# CH32F_V208R-R0.net
KiCad netlist of a schematic drawn in Altium Designer
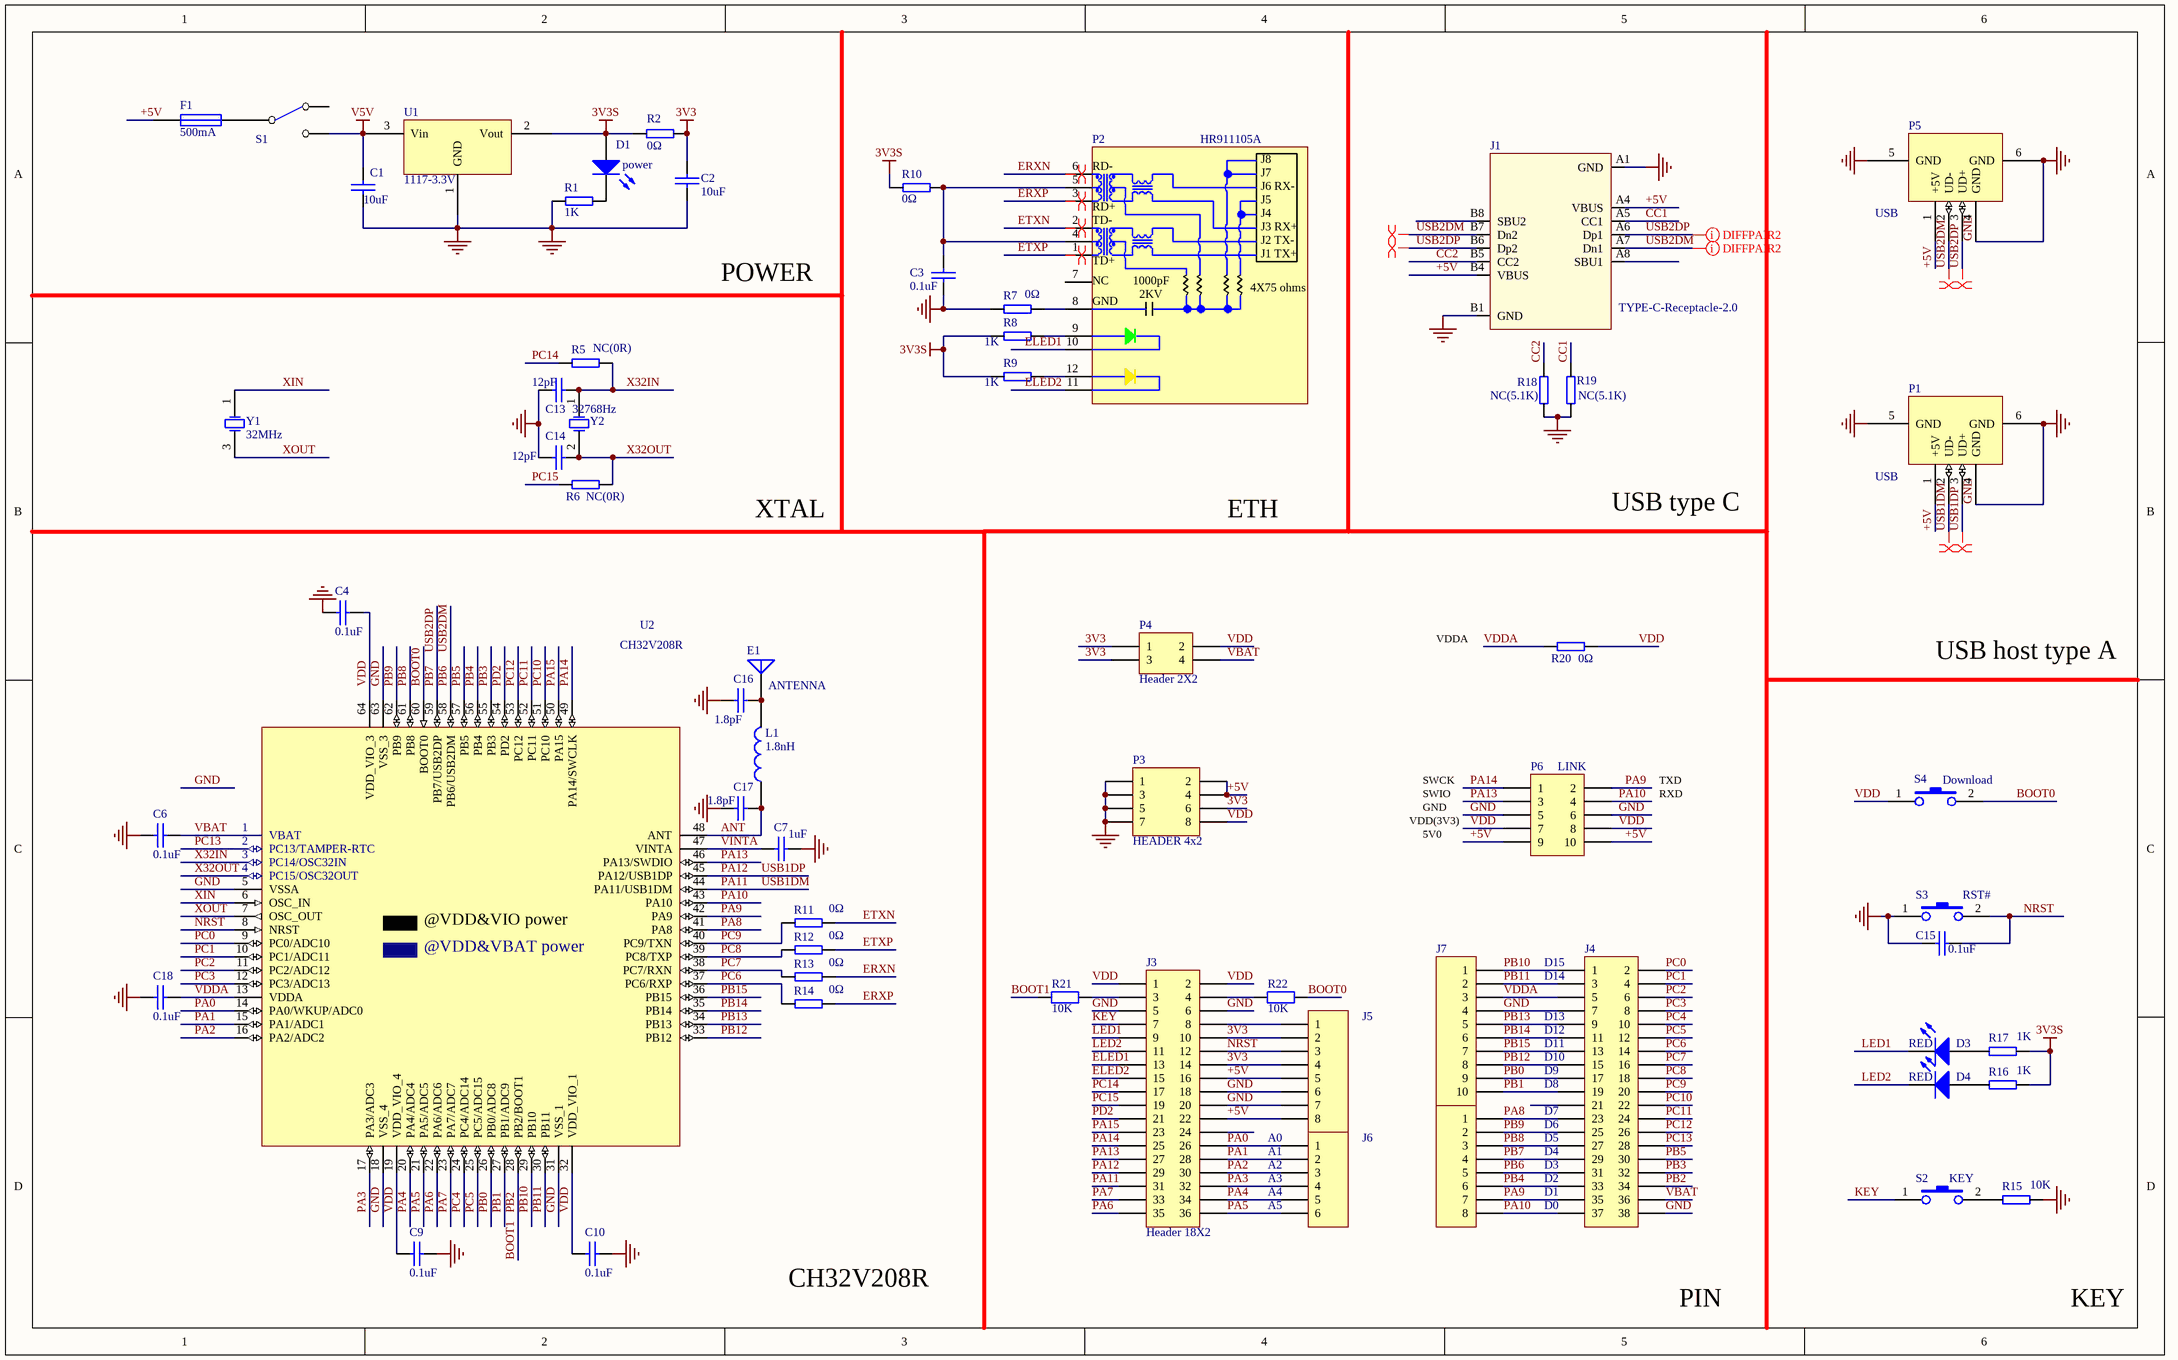
[diagram p0: CH32F&V208R-R0.SchDoc]

(export (version "E")
  (design (tool "Eeschema 10.0.6"))
  (components
    (comp (ref "C1")
      (value "10uF")
      (footprint "3216_C")
      (description "Capacitor")
      (libsource (lib "*") (part "CAP"))
    )
    (comp (ref "C2")
      (value "10uF")
      (footprint "0603_C")
      (description "Capacitor")
      (libsource (lib "*") (part "CAP"))
    )
    (comp (ref "C3")
      (value "0.1uF")
      (footprint "0603_C")
      (description "Capacitor")
      (libsource (lib "*") (part "CAP"))
    )
    (comp (ref "C4")
      (value "0.1uF")
      (footprint "0603_C")
      (description "Capacitor")
      (libsource (lib "") (part "CAP_1"))
    )
    (comp (ref "C6")
      (value "0.1uF")
      (footprint "0603_C")
      (description "Capacitor")
      (libsource (lib "") (part "CAP_1"))
    )
    (comp (ref "C7")
      (value "1uF")
      (footprint "0603_C")
      (description "Capacitor")
      (libsource (lib "") (part "CAP_1"))
    )
    (comp (ref "C9")
      (value "0.1uF")
      (footprint "0603_C")
      (description "Capacitor")
      (libsource (lib "") (part "CAP_1"))
    )
    (comp (ref "C10")
      (value "0.1uF")
      (footprint "0603_C")
      (description "Capacitor")
      (libsource (lib "") (part "CAP_1"))
    )
    (comp (ref "C13")
      (value "12pF")
      (footprint "0603_C")
      (description "Capacitor")
      (libsource (lib "*") (part "CAP"))
    )
    (comp (ref "C14")
      (value "12pF")
      (footprint "0603_C")
      (description "Capacitor")
      (libsource (lib "*") (part "CAP"))
    )
    (comp (ref "C15")
      (value "0.1uF")
      (footprint "0603_C")
      (description "Capacitor")
      (libsource (lib "") (part "CAP_1"))
    )
    (comp (ref "C16")
      (value "1.8pF")
      (footprint "0603_C")
      (description "Capacitor")
      (libsource (lib "") (part "CAP_1"))
    )
    (comp (ref "C17")
      (value "1.8pF")
      (footprint "0603_C")
      (description "Capacitor")
      (libsource (lib "") (part "CAP_1"))
    )
    (comp (ref "C18")
      (value "0.1uF")
      (footprint "0603_C")
      (description "Capacitor")
      (libsource (lib "") (part "CAP_1"))
    )
    (comp (ref "D1")
      (value "power")
      (footprint "0603+")
      (description "Typical INFRARED GaAs LED")
      (fields (field (name "PUBLISHER") "Altium Limited"))
      (libsource (lib "*") (part "LED0"))
    )
    (comp (ref "D3")
      (value "RED")
      (footprint "0603+")
      (description "Typical INFRARED GaAs LED")
      (fields (field (name "PUBLISHER") "Altium Limited"))
      (libsource (lib "*") (part "LED0"))
    )
    (comp (ref "D4")
      (value "RED")
      (footprint "0603+")
      (description "Typical INFRARED GaAs LED")
      (fields (field (name "PUBLISHER") "Altium Limited"))
      (libsource (lib "*") (part "LED0"))
    )
    (comp (ref "E1")
      (value "ANTENNA")
      (footprint "MYPCB:ANT-F-1-2.4G-1.6mmFR4")
      (description "Generic Antenna")
      (libsource (lib "*") (part "ANTENNA"))
    )
    (comp (ref "F1")
      (value "500mA")
      (footprint "0603")
      (description "Fuse")
      (libsource (lib "wch_sch_others") (part "FUSE1"))
    )
    (comp (ref "J1")
      (value "TYPE-C-Receptacle-2.0")
      (footprint "TYPE-C-Receptacle-2.0")
      (description "Type-C USB2.0 母座")
      (libsource (lib "Miscellaneous SCH Lib") (part "TYPE-C-Receptacle-2.0"))
    )
    (comp (ref "J3")
      (value "Header 18X2")
      (footprint "IDC36-2.54mm")
      (description "Header, 18-Pin, Dual row")
      (fields (field (name "PUBLISHER") "Altium Limited"))
      (libsource (lib "Miscellaneous Connectors") (part "Header 18X2"))
    )
    (comp (ref "J4")
      (value "Header 19X2")
      (footprint "IDC38-2.54mm")
      (description "Header, 19-Pin, Dual row")
      (fields (field (name "PUBLISHER") "Altium Limited"))
      (libsource (lib "Miscellaneous Connectors") (part "Header 19X2"))
    )
    (comp (ref "J5")
      (value "Header 8")
      (footprint "SIP8-2.54mm")
      (description "Header, 8-Pin")
      (fields (field (name "PUBLISHER") "Altium Limited"))
      (libsource (lib "Miscellaneous Connectors") (part "Header 8"))
    )
    (comp (ref "J6")
      (value "Header 6")
      (footprint "SIP6-2.54MM")
      (description "Header, 6-Pin")
      (fields (field (name "PUBLISHER") "Altium Limited"))
      (libsource (lib "Miscellaneous Connectors") (part "Header 6"))
    )
    (comp (ref "J7")
      (value "Header 10")
      (footprint "SIP10-2.54mm")
      (description "Header, 10-Pin")
      (fields (field (name "PUBLISHER") "Altium Limited"))
      (libsource (lib "Miscellaneous Connectors") (part "Header 10"))
    )
    (comp (ref "J8")
      (value "Header 8")
      (footprint "SIP8-2.54mm")
      (description "Header, 8-Pin")
      (fields (field (name "PUBLISHER") "Altium Limited"))
      (libsource (lib "") (part "Header 8_1"))
    )
    (comp (ref "L1") (value "1.8nH") (footprint "0603") (libsource (lib "*") (part "INDUCTOR")))
    (comp (ref "P1")
      (value "USB")
      (footprint "USBAF")
      (description "USB Port")
      (libsource (lib "*") (part "USB"))
    )
    (comp (ref "P2") (value "HR911105A") (footprint "HR911105A") (libsource (lib "*") (part "HR911105A")))
    (comp (ref "P3")
      (value "HEADER 4x2")
      (footprint "MYPCB:IDC8-2.54mm")
      (description "Header, 4-Pin, Dual row")
      (libsource (lib "wch_sch_others") (part "HEADER 4x2"))
    )
    (comp (ref "P4")
      (value "Header 2X2")
      (footprint "IDC4-2.54mm")
      (description "Header, 2-Pin, Dual row")
      (fields (field (name "PUBLISHER") "Altium Limited"))
      (libsource (lib "Miscellaneous Connectors") (part "Header 2X2"))
    )
    (comp (ref "P5")
      (value "USB")
      (footprint "USBAF")
      (description "USB Port")
      (libsource (lib "*") (part "USB"))
    )
    (comp (ref "P6")
      (value "LINK")
      (footprint "IDC10-2.54mm")
      (description "Header, 5-Pin, Dual row, Right Angle")
      (fields (field (name "PUBLISHER") "Altium Limited"))
      (libsource (lib "Miscellaneous Connectors") (part "Header 5X2H"))
    )
    (comp (ref "R1") (value "1K") (footprint "0603") (libsource (lib "wch_sch_others") (part "RES")))
    (comp (ref "R2") (value "0Ω") (footprint "0603") (libsource (lib "wch_sch_others") (part "RES")))
    (comp (ref "R5") (value "NC(0R)") (footprint "0603") (libsource (lib "wch_sch_others") (part "RES")))
    (comp (ref "R6") (value "NC(0R)") (footprint "0603") (libsource (lib "wch_sch_others") (part "RES")))
    (comp (ref "R7") (value "0Ω") (footprint "0603") (libsource (lib "wch_sch_others") (part "RES")))
    (comp (ref "R8") (value "1K") (footprint "0603") (libsource (lib "wch_sch_others") (part "RES")))
    (comp (ref "R9") (value "1K") (footprint "0603") (libsource (lib "wch_sch_others") (part "RES")))
    (comp (ref "R10") (value "0Ω") (footprint "0603") (libsource (lib "wch_sch_others") (part "RES")))
    (comp (ref "R11") (value "0Ω") (footprint "0603") (libsource (lib "wch_sch_others") (part "RES")))
    (comp (ref "R12") (value "0Ω") (footprint "0603") (libsource (lib "wch_sch_others") (part "RES")))
    (comp (ref "R13") (value "0Ω") (footprint "0603") (libsource (lib "wch_sch_others") (part "RES")))
    (comp (ref "R14") (value "0Ω") (footprint "0603") (libsource (lib "wch_sch_others") (part "RES")))
    (comp (ref "R15") (value "10K") (footprint "0603") (libsource (lib "wch_sch_others") (part "RES")))
    (comp (ref "R16") (value "1K") (footprint "0603") (libsource (lib "wch_sch_others") (part "RES")))
    (comp (ref "R17") (value "1K") (footprint "0603") (libsource (lib "wch_sch_others") (part "RES")))
    (comp (ref "R18") (value "NC(5.1K)") (footprint "0603") (libsource (lib "wch_sch_others") (part "RES")))
    (comp (ref "R19") (value "NC(5.1K)") (footprint "0603") (libsource (lib "wch_sch_others") (part "RES")))
    (comp (ref "R20") (value "0Ω") (footprint "0603") (libsource (lib "*") (part "R")))
    (comp (ref "R21")
      (value "10K")
      (footprint "0603")
      (description "Resistor")
      (libsource (lib "Miscellaneous Devices") (part "Res2"))
    )
    (comp (ref "R22")
      (value "10K")
      (footprint "0603")
      (description "Resistor")
      (libsource (lib "Miscellaneous Devices") (part "Res2"))
    )
    (comp (ref "S1") (value "SW SPDT") (footprint "SW1") (libsource (lib "*") (part "SW SPDT")))
    (comp (ref "S2")
      (value "KEY")
      (footprint "SMD_6.1x3.65x2.5mm-KEY")
      (libsource (lib "wch_sch_others") (part "KEY1"))
    )
    (comp (ref "S3")
      (value "RST#")
      (footprint "SMD_6.1x3.65x2.5mm-KEY")
      (libsource (lib "wch_sch_others") (part "KEY1"))
    )
    (comp (ref "S4")
      (value "Download")
      (footprint "SMD_6.1x3.65x2.5mm-KEY")
      (libsource (lib "wch_sch_others") (part "KEY1"))
    )
    (comp (ref "U1")
      (value "1117-3.3V")
      (footprint "SOT-223")
      (libsource (lib "wch_sch_others") (part "1117-3.3V"))
    )
    (comp (ref "U2")
      (value "CH32V208R")
      (footprint "LQFP64M_10x10")
      (description "RISC-V BLE5.3 MCU, 10M Ethernet, 2*USB, CAN")
      (libsource (lib "CHXXX") (part "CH32V208R"))
    )
    (comp (ref "Y1")
      (value "32MHz")
      (footprint "XT3225")
      (description "Crystal Oscillator")
      (fields (field (name "PUBLISHER") "Altium Limited"))
      (libsource (lib "") (part "XTAL_1"))
    )
    (comp (ref "Y2")
      (value "32768Hz")
      (footprint "FC-135")
      (description "Crystal Oscillator")
      (fields (field (name "PUBLISHER") "Altium Limited"))
      (libsource (lib "*") (part "XTAL"))
    )
  )
  (nets
    (net (code "1") (name "/+5V") (class "Default")
      (node (ref "F1") (pin "1") (pinfunction "1_1") (pintype "passive"))
      (node (ref "J1") (pin "A4") (pinfunction "VBUS_A4") (pintype "passive"))
      (node (ref "J1") (pin "B4") (pinfunction "VBUS_B4") (pintype "passive"))
      (node (ref "J3") (pin "16") (pinfunction "16_16") (pintype "passive"))
      (node (ref "J3") (pin "22") (pinfunction "22_22") (pintype "passive"))
      (node (ref "J5") (pin "5") (pinfunction "5_5") (pintype "passive"))
      (node (ref "J5") (pin "8") (pinfunction "8_8") (pintype "passive"))
      (node (ref "P1") (pin "1") (pinfunction "+5V_1") (pintype "power_in"))
      (node (ref "P3") (pin "2") (pinfunction "2_2") (pintype "passive"))
      (node (ref "P3") (pin "4") (pinfunction "4_4") (pintype "passive"))
      (node (ref "P5") (pin "1") (pinfunction "+5V_1") (pintype "power_in"))
      (node (ref "P6") (pin "10") (pinfunction "10_10") (pintype "passive"))
      (node (ref "P6") (pin "9") (pinfunction "9_9") (pintype "passive"))
    )
    (net (code "2") (name "/ANT") (class "Default")
      (node (ref "C17") (pin "2") (pinfunction "2_2") (pintype "passive"))
      (node (ref "L1") (pin "1") (pinfunction "1_1") (pintype "passive"))
      (node (ref "U2") (pin "48") (pinfunction "ANT_48") (pintype "power_in"))
    )
    (net (code "3") (name "/BOOT0") (class "Default")
      (node (ref "R22") (pin "2") (pinfunction "2_2") (pintype "passive"))
      (node (ref "S4") (pin "2") (pinfunction "2_2") (pintype "passive"))
      (node (ref "U2") (pin "60") (pinfunction "BOOT0_60") (pintype "input"))
    )
    (net (code "4") (name "/BOOT1") (class "Default")
      (node (ref "J4") (pin "34") (pinfunction "34_34") (pintype "passive"))
      (node (ref "R21") (pin "1") (pinfunction "1_1") (pintype "passive"))
      (node (ref "U2") (pin "28") (pinfunction "PB2/BOOT1_28") (pintype "bidirectional"))
    )
    (net (code "5") (name "/CC1") (class "Default")
      (node (ref "J1") (pin "A5") (pinfunction "CC1_A5") (pintype "passive"))
      (node (ref "R19") (pin "1") (pintype "passive"))
    )
    (net (code "6") (name "/CC2") (class "Default")
      (node (ref "J1") (pin "B5") (pinfunction "CC2_B5") (pintype "passive"))
      (node (ref "R18") (pin "1") (pintype "passive"))
    )
    (net (code "7") (name "/ELED1") (class "Default")
      (node (ref "J3") (pin "13") (pinfunction "13_13") (pintype "passive"))
      (node (ref "P2") (pin "10") (pintype "passive"))
    )
    (net (code "8") (name "/ELED2") (class "Default")
      (node (ref "J3") (pin "15") (pinfunction "15_15") (pintype "passive"))
      (node (ref "P2") (pin "11") (pintype "passive"))
    )
    (net (code "9") (name "/ERXN") (class "Default")
      (node (ref "P2") (pin "6") (pintype "passive"))
      (node (ref "R13") (pin "2") (pintype "passive"))
    )
    (net (code "10") (name "/ERXP") (class "Default")
      (node (ref "P2") (pin "3") (pintype "passive"))
      (node (ref "R14") (pin "2") (pintype "passive"))
    )
    (net (code "11") (name "/ETXN") (class "Default")
      (node (ref "P2") (pin "2") (pintype "passive"))
      (node (ref "R11") (pin "2") (pintype "passive"))
    )
    (net (code "12") (name "/ETXP") (class "Default")
      (node (ref "P2") (pin "1") (pintype "passive"))
      (node (ref "R12") (pin "2") (pintype "passive"))
    )
    (net (code "13") (name "/KEY") (class "Default")
      (node (ref "J3") (pin "7") (pinfunction "7_7") (pintype "passive"))
      (node (ref "S2") (pin "1") (pinfunction "1_1") (pintype "passive"))
    )
    (net (code "14") (name "/LED1") (class "Default")
      (node (ref "D3") (pin "2") (pinfunction "K_2") (pintype "passive"))
      (node (ref "J3") (pin "9") (pinfunction "9_9") (pintype "passive"))
    )
    (net (code "15") (name "/LED2") (class "Default")
      (node (ref "D4") (pin "2") (pinfunction "K_2") (pintype "passive"))
      (node (ref "J3") (pin "11") (pinfunction "11_11") (pintype "passive"))
    )
    (net (code "16") (name "/NRST") (class "Default")
      (node (ref "C15") (pin "2") (pinfunction "2_2") (pintype "passive"))
      (node (ref "J3") (pin "12") (pinfunction "12_12") (pintype "passive"))
      (node (ref "J5") (pin "3") (pinfunction "3_3") (pintype "passive"))
      (node (ref "S3") (pin "2") (pinfunction "2_2") (pintype "passive"))
      (node (ref "U2") (pin "8") (pinfunction "NRST_8") (pintype "input"))
    )
    (net (code "17") (name "/PA0") (class "Default")
      (node (ref "J3") (pin "26") (pinfunction "26_26") (pintype "passive"))
      (node (ref "J6") (pin "1") (pinfunction "1_1") (pintype "passive"))
      (node (ref "U2") (pin "14") (pinfunction "PA0/WKUP/ADC0_14") (pintype "bidirectional"))
    )
    (net (code "18") (name "/PA1") (class "Default")
      (node (ref "J3") (pin "28") (pinfunction "28_28") (pintype "passive"))
      (node (ref "J6") (pin "2") (pinfunction "2_2") (pintype "passive"))
      (node (ref "U2") (pin "15") (pinfunction "PA1/ADC1_15") (pintype "bidirectional"))
    )
    (net (code "19") (name "/PA2") (class "Default")
      (node (ref "J3") (pin "30") (pinfunction "30_30") (pintype "passive"))
      (node (ref "J6") (pin "3") (pinfunction "3_3") (pintype "passive"))
      (node (ref "U2") (pin "16") (pinfunction "PA2/ADC2_16") (pintype "bidirectional"))
    )
    (net (code "20") (name "/PA3") (class "Default")
      (node (ref "J3") (pin "32") (pinfunction "32_32") (pintype "passive"))
      (node (ref "J6") (pin "4") (pinfunction "4_4") (pintype "passive"))
      (node (ref "U2") (pin "17") (pinfunction "PA3/ADC3_17") (pintype "bidirectional"))
    )
    (net (code "21") (name "/PA4") (class "Default")
      (node (ref "J3") (pin "34") (pinfunction "34_34") (pintype "passive"))
      (node (ref "J6") (pin "5") (pinfunction "5_5") (pintype "passive"))
      (node (ref "U2") (pin "20") (pinfunction "PA4/ADC4_20") (pintype "bidirectional"))
    )
    (net (code "22") (name "/PA5") (class "Default")
      (node (ref "J3") (pin "36") (pinfunction "36_36") (pintype "passive"))
      (node (ref "J6") (pin "6") (pinfunction "6_6") (pintype "passive"))
      (node (ref "U2") (pin "21") (pinfunction "PA5/ADC5_21") (pintype "bidirectional"))
    )
    (net (code "23") (name "/PA6") (class "Default")
      (node (ref "J3") (pin "35") (pinfunction "35_35") (pintype "passive"))
      (node (ref "U2") (pin "22") (pinfunction "PA6/ADC6_22") (pintype "bidirectional"))
    )
    (net (code "24") (name "/PA7") (class "Default")
      (node (ref "J3") (pin "33") (pinfunction "33_33") (pintype "passive"))
      (node (ref "U2") (pin "23") (pinfunction "PA7/ADC7_23") (pintype "bidirectional"))
    )
    (net (code "25") (name "/PA8") (class "Default")
      (node (ref "J4") (pin "23") (pinfunction "23_23") (pintype "passive"))
      (node (ref "J8") (pin "1") (pinfunction "1_1") (pintype "passive"))
      (node (ref "U2") (pin "41") (pinfunction "PA8_41") (pintype "bidirectional"))
    )
    (net (code "26") (name "/PA9") (class "Default")
      (node (ref "J4") (pin "35") (pinfunction "35_35") (pintype "passive"))
      (node (ref "J8") (pin "7") (pinfunction "7_7") (pintype "passive"))
      (node (ref "P6") (pin "2") (pinfunction "2_2") (pintype "passive"))
      (node (ref "U2") (pin "42") (pinfunction "PA9_42") (pintype "bidirectional"))
    )
    (net (code "27") (name "/PA10") (class "Default")
      (node (ref "J4") (pin "37") (pinfunction "37_37") (pintype "passive"))
      (node (ref "J8") (pin "8") (pinfunction "8_8") (pintype "passive"))
      (node (ref "P6") (pin "4") (pinfunction "4_4") (pintype "passive"))
      (node (ref "U2") (pin "43") (pinfunction "PA10_43") (pintype "bidirectional"))
    )
    (net (code "28") (name "/PA11") (class "Default")
      (node (ref "J3") (pin "31") (pinfunction "31_31") (pintype "passive"))
      (node (ref "P1") (pin "2") (pinfunction "UD-_2") (pintype "bidirectional"))
      (node (ref "U2") (pin "44") (pinfunction "PA11/USB1DM_44") (pintype "bidirectional"))
    )
    (net (code "29") (name "/PA12") (class "Default")
      (node (ref "J3") (pin "29") (pinfunction "29_29") (pintype "passive"))
      (node (ref "P1") (pin "3") (pinfunction "UD+_3") (pintype "bidirectional"))
      (node (ref "U2") (pin "45") (pinfunction "PA12/USB1DP_45") (pintype "bidirectional"))
    )
    (net (code "30") (name "/PA13") (class "Default")
      (node (ref "J3") (pin "27") (pinfunction "27_27") (pintype "passive"))
      (node (ref "P6") (pin "3") (pinfunction "3_3") (pintype "passive"))
      (node (ref "U2") (pin "46") (pinfunction "PA13/SWDIO_46") (pintype "bidirectional"))
    )
    (net (code "31") (name "/PA14") (class "Default")
      (node (ref "J3") (pin "25") (pinfunction "25_25") (pintype "passive"))
      (node (ref "P6") (pin "1") (pinfunction "1_1") (pintype "passive"))
      (node (ref "U2") (pin "49") (pinfunction "PA14/SWCLK_49") (pintype "bidirectional"))
    )
    (net (code "32") (name "/PA15") (class "Default")
      (node (ref "J3") (pin "23") (pinfunction "23_23") (pintype "passive"))
      (node (ref "U2") (pin "50") (pinfunction "PA15_50") (pintype "bidirectional"))
    )
    (net (code "33") (name "/PB0") (class "Default")
      (node (ref "J4") (pin "17") (pinfunction "17_17") (pintype "passive"))
      (node (ref "J7") (pin "9") (pinfunction "9_9") (pintype "passive"))
      (node (ref "U2") (pin "26") (pinfunction "PB0/ADC8_26") (pintype "bidirectional"))
    )
    (net (code "34") (name "/PB1") (class "Default")
      (node (ref "J4") (pin "19") (pinfunction "19_19") (pintype "passive"))
      (node (ref "J7") (pin "10") (pinfunction "10_10") (pintype "passive"))
      (node (ref "U2") (pin "27") (pinfunction "PB1/ADC9_27") (pintype "bidirectional"))
    )
    (net (code "35") (name "/PB3") (class "Default")
      (node (ref "J4") (pin "32") (pinfunction "32_32") (pintype "passive"))
      (node (ref "U2") (pin "55") (pinfunction "PB3_55") (pintype "bidirectional"))
    )
    (net (code "36") (name "/PB4") (class "Default")
      (node (ref "J4") (pin "33") (pinfunction "33_33") (pintype "passive"))
      (node (ref "J8") (pin "6") (pinfunction "6_6") (pintype "passive"))
      (node (ref "U2") (pin "56") (pinfunction "PB4_56") (pintype "bidirectional"))
    )
    (net (code "37") (name "/PB5") (class "Default")
      (node (ref "J4") (pin "30") (pinfunction "30_30") (pintype "passive"))
      (node (ref "U2") (pin "57") (pinfunction "PB5_57") (pintype "bidirectional"))
    )
    (net (code "38") (name "/PB6") (class "Default")
      (node (ref "J1") (pin "A7") (pinfunction "Dn1_A7") (pintype "passive"))
      (node (ref "J1") (pin "B7") (pinfunction "Dn2_B7") (pintype "passive"))
      (node (ref "J4") (pin "31") (pinfunction "31_31") (pintype "passive"))
      (node (ref "J8") (pin "5") (pinfunction "5_5") (pintype "passive"))
      (node (ref "P5") (pin "2") (pinfunction "UD-_2") (pintype "bidirectional"))
      (node (ref "U2") (pin "58") (pinfunction "PB6/USB2DM_58") (pintype "bidirectional"))
    )
    (net (code "39") (name "/PB7") (class "Default")
      (node (ref "J1") (pin "A6") (pinfunction "Dp1_A6") (pintype "passive"))
      (node (ref "J1") (pin "B6") (pinfunction "Dp2_B6") (pintype "passive"))
      (node (ref "J4") (pin "29") (pinfunction "29_29") (pintype "passive"))
      (node (ref "J8") (pin "4") (pinfunction "4_4") (pintype "passive"))
      (node (ref "P5") (pin "3") (pinfunction "UD+_3") (pintype "bidirectional"))
      (node (ref "U2") (pin "59") (pinfunction "PB7/USB2DP_59") (pintype "bidirectional"))
    )
    (net (code "40") (name "/PB8") (class "Default")
      (node (ref "J4") (pin "27") (pinfunction "27_27") (pintype "passive"))
      (node (ref "J8") (pin "3") (pinfunction "3_3") (pintype "passive"))
      (node (ref "U2") (pin "61") (pinfunction "PB8_61") (pintype "bidirectional"))
    )
    (net (code "41") (name "/PB9") (class "Default")
      (node (ref "J4") (pin "25") (pinfunction "25_25") (pintype "passive"))
      (node (ref "J8") (pin "2") (pinfunction "2_2") (pintype "passive"))
      (node (ref "U2") (pin "62") (pinfunction "PB9_62") (pintype "bidirectional"))
    )
    (net (code "42") (name "/PB10") (class "Default")
      (node (ref "J4") (pin "1") (pinfunction "1_1") (pintype "passive"))
      (node (ref "J7") (pin "1") (pinfunction "1_1") (pintype "passive"))
      (node (ref "U2") (pin "29") (pinfunction "PB10_29") (pintype "bidirectional"))
    )
    (net (code "43") (name "/PB11") (class "Default")
      (node (ref "J4") (pin "3") (pinfunction "3_3") (pintype "passive"))
      (node (ref "J7") (pin "2") (pinfunction "2_2") (pintype "passive"))
      (node (ref "U2") (pin "30") (pinfunction "PB11_30") (pintype "bidirectional"))
    )
    (net (code "44") (name "/PB12") (class "Default")
      (node (ref "J4") (pin "15") (pinfunction "15_15") (pintype "passive"))
      (node (ref "J7") (pin "8") (pinfunction "8_8") (pintype "passive"))
      (node (ref "U2") (pin "33") (pinfunction "PB12_33") (pintype "bidirectional"))
    )
    (net (code "45") (name "/PB13") (class "Default")
      (node (ref "J4") (pin "9") (pinfunction "9_9") (pintype "passive"))
      (node (ref "J7") (pin "5") (pinfunction "5_5") (pintype "passive"))
      (node (ref "U2") (pin "34") (pinfunction "PB13_34") (pintype "bidirectional"))
    )
    (net (code "46") (name "/PB14") (class "Default")
      (node (ref "J4") (pin "11") (pinfunction "11_11") (pintype "passive"))
      (node (ref "J7") (pin "6") (pinfunction "6_6") (pintype "passive"))
      (node (ref "U2") (pin "35") (pinfunction "PB14_35") (pintype "bidirectional"))
    )
    (net (code "47") (name "/PB15") (class "Default")
      (node (ref "J4") (pin "13") (pinfunction "13_13") (pintype "passive"))
      (node (ref "J7") (pin "7") (pinfunction "7_7") (pintype "passive"))
      (node (ref "U2") (pin "36") (pinfunction "PB15_36") (pintype "bidirectional"))
    )
    (net (code "48") (name "/PC0") (class "Default")
      (node (ref "J4") (pin "2") (pinfunction "2_2") (pintype "passive"))
      (node (ref "U2") (pin "9") (pinfunction "PC0/ADC10_9") (pintype "bidirectional"))
    )
    (net (code "49") (name "/PC1") (class "Default")
      (node (ref "J4") (pin "4") (pinfunction "4_4") (pintype "passive"))
      (node (ref "U2") (pin "10") (pinfunction "PC1/ADC11_10") (pintype "bidirectional"))
    )
    (net (code "50") (name "/PC2") (class "Default")
      (node (ref "J4") (pin "6") (pinfunction "6_6") (pintype "passive"))
      (node (ref "U2") (pin "11") (pinfunction "PC2/ADC12_11") (pintype "bidirectional"))
    )
    (net (code "51") (name "/PC3") (class "Default")
      (node (ref "J4") (pin "8") (pinfunction "8_8") (pintype "passive"))
      (node (ref "U2") (pin "12") (pinfunction "PC3/ADC13_12") (pintype "bidirectional"))
    )
    (net (code "52") (name "/PC4") (class "Default")
      (node (ref "J4") (pin "10") (pinfunction "10_10") (pintype "passive"))
      (node (ref "U2") (pin "24") (pinfunction "PC4/ADC14_24") (pintype "bidirectional"))
    )
    (net (code "53") (name "/PC5") (class "Default")
      (node (ref "J4") (pin "12") (pinfunction "12_12") (pintype "passive"))
      (node (ref "U2") (pin "25") (pinfunction "PC5/ADC15_25") (pintype "bidirectional"))
    )
    (net (code "54") (name "/PC6") (class "Default")
      (node (ref "J4") (pin "14") (pinfunction "14_14") (pintype "passive"))
      (node (ref "R14") (pin "1") (pintype "passive"))
      (node (ref "U2") (pin "37") (pinfunction "PC6/RXP_37") (pintype "bidirectional"))
    )
    (net (code "55") (name "/PC7") (class "Default")
      (node (ref "J4") (pin "16") (pinfunction "16_16") (pintype "passive"))
      (node (ref "R13") (pin "1") (pintype "passive"))
      (node (ref "U2") (pin "38") (pinfunction "PC7/RXN_38") (pintype "bidirectional"))
    )
    (net (code "56") (name "/PC8") (class "Default")
      (node (ref "J4") (pin "18") (pinfunction "18_18") (pintype "passive"))
      (node (ref "R12") (pin "1") (pintype "passive"))
      (node (ref "U2") (pin "39") (pinfunction "PC8/TXP_39") (pintype "bidirectional"))
    )
    (net (code "57") (name "/PC9") (class "Default")
      (node (ref "J4") (pin "20") (pinfunction "20_20") (pintype "passive"))
      (node (ref "R11") (pin "1") (pintype "passive"))
      (node (ref "U2") (pin "40") (pinfunction "PC9/TXN_40") (pintype "bidirectional"))
    )
    (net (code "58") (name "/PC10") (class "Default")
      (node (ref "J4") (pin "22") (pinfunction "22_22") (pintype "passive"))
      (node (ref "U2") (pin "51") (pinfunction "PC10_51") (pintype "bidirectional"))
    )
    (net (code "59") (name "/PC11") (class "Default")
      (node (ref "J4") (pin "24") (pinfunction "24_24") (pintype "passive"))
      (node (ref "U2") (pin "52") (pinfunction "PC11_52") (pintype "bidirectional"))
    )
    (net (code "60") (name "/PC12") (class "Default")
      (node (ref "J4") (pin "26") (pinfunction "26_26") (pintype "passive"))
      (node (ref "U2") (pin "53") (pinfunction "PC12_53") (pintype "bidirectional"))
    )
    (net (code "61") (name "/PC13") (class "Default")
      (node (ref "J4") (pin "28") (pinfunction "28_28") (pintype "passive"))
      (node (ref "U2") (pin "2") (pinfunction "PC13/TAMPER-RTC_2") (pintype "bidirectional"))
    )
    (net (code "62") (name "/PC14") (class "Default")
      (node (ref "J3") (pin "17") (pinfunction "17_17") (pintype "passive"))
      (node (ref "R5") (pin "1") (pintype "passive"))
    )
    (net (code "63") (name "/PC15") (class "Default")
      (node (ref "J3") (pin "19") (pinfunction "19_19") (pintype "passive"))
      (node (ref "R6") (pin "1") (pintype "passive"))
    )
    (net (code "64") (name "/PD2") (class "Default")
      (node (ref "J3") (pin "21") (pinfunction "21_21") (pintype "passive"))
      (node (ref "U2") (pin "54") (pinfunction "PD2_54") (pintype "bidirectional"))
    )
    (net (code "65") (name "/VBAT") (class "Default")
      (node (ref "C6") (pin "1") (pinfunction "1_1") (pintype "passive"))
      (node (ref "J4") (pin "36") (pinfunction "36_36") (pintype "passive"))
      (node (ref "P4") (pin "4") (pinfunction "4_4") (pintype "passive"))
      (node (ref "U2") (pin "1") (pinfunction "VBAT_1") (pintype "power_in"))
    )
    (net (code "66") (name "/VDD") (class "Default")
      (node (ref "C10") (pin "2") (pinfunction "2_2") (pintype "passive"))
      (node (ref "C4") (pin "1") (pinfunction "1_1") (pintype "passive"))
      (node (ref "C9") (pin "2") (pinfunction "2_2") (pintype "passive"))
      (node (ref "J3") (pin "1") (pinfunction "1_1") (pintype "passive"))
      (node (ref "J3") (pin "2") (pinfunction "2_2") (pintype "passive"))
      (node (ref "P3") (pin "8") (pinfunction "8_8") (pintype "passive"))
      (node (ref "P4") (pin "2") (pinfunction "2_2") (pintype "passive"))
      (node (ref "P6") (pin "7") (pinfunction "7_7") (pintype "passive"))
      (node (ref "P6") (pin "8") (pinfunction "8_8") (pintype "passive"))
      (node (ref "R20") (pin "1") (pinfunction "1_1") (pintype "passive"))
      (node (ref "S4") (pin "1") (pinfunction "1_1") (pintype "passive"))
      (node (ref "U2") (pin "19") (pinfunction "VDD_VIO_4_19") (pintype "power_in"))
      (node (ref "U2") (pin "32") (pinfunction "VDD_VIO_1_32") (pintype "power_in"))
      (node (ref "U2") (pin "64") (pinfunction "VDD_VIO_3_64") (pintype "power_in"))
    )
    (net (code "67") (name "/VDDA") (class "Default")
      (node (ref "C18") (pin "1") (pinfunction "1_1") (pintype "passive"))
      (node (ref "J4") (pin "5") (pinfunction "5_5") (pintype "passive"))
      (node (ref "J7") (pin "3") (pinfunction "3_3") (pintype "passive"))
      (node (ref "R20") (pin "2") (pinfunction "2_2") (pintype "passive"))
      (node (ref "U2") (pin "13") (pinfunction "VDDA_13") (pintype "power_in"))
    )
    (net (code "68") (name "/VINTA") (class "Default")
      (node (ref "C7") (pin "1") (pinfunction "1_1") (pintype "passive"))
      (node (ref "U2") (pin "47") (pinfunction "VINTA_47") (pintype "power_in"))
    )
    (net (code "69") (name "/X32IN") (class "Default")
      (node (ref "C13") (pin "2") (pinfunction "2_2") (pintype "passive"))
      (node (ref "R5") (pin "2") (pintype "passive"))
      (node (ref "U2") (pin "3") (pinfunction "PC14/OSC32IN_3") (pintype "bidirectional"))
      (node (ref "Y2") (pin "1") (pinfunction "OSC1_1") (pintype "passive"))
    )
    (net (code "70") (name "/X32OUT") (class "Default")
      (node (ref "C14") (pin "2") (pinfunction "2_2") (pintype "passive"))
      (node (ref "R6") (pin "2") (pintype "passive"))
      (node (ref "U2") (pin "4") (pinfunction "PC15/OSC32OUT_4") (pintype "bidirectional"))
      (node (ref "Y2") (pin "2") (pinfunction "OSC2_2") (pintype "passive"))
    )
    (net (code "71") (name "/XIN") (class "Default")
      (node (ref "U2") (pin "6") (pinfunction "OSC_IN_6") (pintype "input"))
      (node (ref "Y1") (pin "1") (pinfunction "OSC1_1") (pintype "passive"))
    )
    (net (code "72") (name "/XOUT") (class "Default")
      (node (ref "U2") (pin "7") (pinfunction "OSC_OUT_7") (pintype "output"))
      (node (ref "Y1") (pin "3") (pinfunction "OSC2_3") (pintype "passive"))
    )
    (net (code "73") (name "3V3") (class "Default")
      (node (ref "C2") (pin "1") (pinfunction "1_1") (pintype "passive"))
      (node (ref "J3") (pin "10") (pinfunction "10_10") (pintype "passive"))
      (node (ref "J3") (pin "14") (pinfunction "14_14") (pintype "passive"))
      (node (ref "J5") (pin "2") (pinfunction "2_2") (pintype "passive"))
      (node (ref "J5") (pin "4") (pinfunction "4_4") (pintype "passive"))
      (node (ref "P3") (pin "6") (pinfunction "6_6") (pintype "passive"))
      (node (ref "P4") (pin "1") (pinfunction "1_1") (pintype "passive"))
      (node (ref "P4") (pin "3") (pinfunction "3_3") (pintype "passive"))
      (node (ref "R2") (pin "1") (pintype "passive"))
    )
    (net (code "74") (name "3V3S") (class "Default")
      (node (ref "D1") (pin "1") (pinfunction "A_1") (pintype "passive"))
      (node (ref "R10") (pin "2") (pintype "passive"))
      (node (ref "R16") (pin "1") (pintype "passive"))
      (node (ref "R17") (pin "1") (pintype "passive"))
      (node (ref "R2") (pin "2") (pintype "passive"))
      (node (ref "R8") (pin "1") (pintype "passive"))
      (node (ref "R9") (pin "1") (pintype "passive"))
      (node (ref "U1") (pin "2") (pinfunction "Vout_2") (pintype "passive"))
    )
    (net (code "75") (name "GND") (class "Default")
      (node (ref "C1") (pin "2") (pinfunction "2_2") (pintype "passive"))
      (node (ref "C10") (pin "1") (pinfunction "1_1") (pintype "passive"))
      (node (ref "C13") (pin "1") (pinfunction "1_1") (pintype "passive"))
      (node (ref "C14") (pin "1") (pinfunction "1_1") (pintype "passive"))
      (node (ref "C15") (pin "1") (pinfunction "1_1") (pintype "passive"))
      (node (ref "C16") (pin "1") (pinfunction "1_1") (pintype "passive"))
      (node (ref "C17") (pin "1") (pinfunction "1_1") (pintype "passive"))
      (node (ref "C18") (pin "2") (pinfunction "2_2") (pintype "passive"))
      (node (ref "C2") (pin "2") (pinfunction "2_2") (pintype "passive"))
      (node (ref "C3") (pin "1") (pinfunction "1_1") (pintype "passive"))
      (node (ref "C4") (pin "2") (pinfunction "2_2") (pintype "passive"))
      (node (ref "C6") (pin "2") (pinfunction "2_2") (pintype "passive"))
      (node (ref "C7") (pin "2") (pinfunction "2_2") (pintype "passive"))
      (node (ref "C9") (pin "1") (pinfunction "1_1") (pintype "passive"))
      (node (ref "J1") (pin "A1") (pinfunction "GND_A1") (pintype "passive"))
      (node (ref "J1") (pin "B1") (pinfunction "GND_B1") (pintype "passive"))
      (node (ref "J3") (pin "18") (pinfunction "18_18") (pintype "passive"))
      (node (ref "J3") (pin "20") (pinfunction "20_20") (pintype "passive"))
      (node (ref "J3") (pin "5") (pinfunction "5_5") (pintype "passive"))
      (node (ref "J3") (pin "6") (pinfunction "6_6") (pintype "passive"))
      (node (ref "J4") (pin "38") (pinfunction "38_38") (pintype "passive"))
      (node (ref "J4") (pin "7") (pinfunction "7_7") (pintype "passive"))
      (node (ref "J5") (pin "6") (pinfunction "6_6") (pintype "passive"))
      (node (ref "J5") (pin "7") (pinfunction "7_7") (pintype "passive"))
      (node (ref "J7") (pin "4") (pinfunction "4_4") (pintype "passive"))
      (node (ref "P1") (pin "4") (pinfunction "GND_4") (pintype "power_in"))
      (node (ref "P1") (pin "5") (pinfunction "GND_5") (pintype "power_in"))
      (node (ref "P1") (pin "6") (pinfunction "GND_6") (pintype "power_in"))
      (node (ref "P3") (pin "1") (pinfunction "1_1") (pintype "passive"))
      (node (ref "P3") (pin "3") (pinfunction "3_3") (pintype "passive"))
      (node (ref "P3") (pin "5") (pinfunction "5_5") (pintype "passive"))
      (node (ref "P3") (pin "7") (pinfunction "7_7") (pintype "passive"))
      (node (ref "P5") (pin "4") (pinfunction "GND_4") (pintype "power_in"))
      (node (ref "P5") (pin "5") (pinfunction "GND_5") (pintype "power_in"))
      (node (ref "P5") (pin "6") (pinfunction "GND_6") (pintype "power_in"))
      (node (ref "P6") (pin "5") (pinfunction "5_5") (pintype "passive"))
      (node (ref "P6") (pin "6") (pinfunction "6_6") (pintype "passive"))
      (node (ref "R1") (pin "1") (pintype "passive"))
      (node (ref "R15") (pin "1") (pintype "passive"))
      (node (ref "R18") (pin "2") (pintype "passive"))
      (node (ref "R19") (pin "2") (pintype "passive"))
      (node (ref "R7") (pin "1") (pintype "passive"))
      (node (ref "S3") (pin "1") (pinfunction "1_1") (pintype "passive"))
      (node (ref "U1") (pin "1") (pinfunction "GND_1") (pintype "passive"))
      (node (ref "U2") (pin "18") (pinfunction "VSS_4_18") (pintype "power_in"))
      (node (ref "U2") (pin "31") (pinfunction "VSS_1_31") (pintype "power_in"))
      (node (ref "U2") (pin "5") (pinfunction "VSSA_5") (pintype "power_in"))
      (node (ref "U2") (pin "63") (pinfunction "VSS_3_63") (pintype "power_in"))
    )
    (net (code "76") (name "Net-(C3-Pad2)") (class "Default")
      (node (ref "C3") (pin "2") (pinfunction "2_2") (pintype "passive"))
      (node (ref "P2") (pin "4") (pintype "passive"))
      (node (ref "P2") (pin "5") (pintype "passive"))
      (node (ref "R10") (pin "1") (pintype "passive"))
    )
    (net (code "77") (name "Net-(D1-K)") (class "Default")
      (node (ref "D1") (pin "2") (pinfunction "K_2") (pintype "passive"))
      (node (ref "R1") (pin "2") (pintype "passive"))
    )
    (net (code "78") (name "Net-(D3-A)") (class "Default")
      (node (ref "D3") (pin "1") (pinfunction "A_1") (pintype "passive"))
      (node (ref "R17") (pin "2") (pintype "passive"))
    )
    (net (code "79") (name "Net-(D4-A)") (class "Default")
      (node (ref "D4") (pin "1") (pinfunction "A_1") (pintype "passive"))
      (node (ref "R16") (pin "2") (pintype "passive"))
    )
    (net (code "80") (name "Net-(E1-A)") (class "Default")
      (node (ref "C16") (pin "2") (pinfunction "2_2") (pintype "passive"))
      (node (ref "E1") (pin "1") (pinfunction "A_1") (pintype "passive"))
      (node (ref "L1") (pin "2") (pinfunction "2_2") (pintype "passive"))
    )
    (net (code "81") (name "Net-(J3-Pad3)") (class "Default")
      (node (ref "J3") (pin "3") (pinfunction "3_3") (pintype "passive"))
      (node (ref "R21") (pin "2") (pinfunction "2_2") (pintype "passive"))
    )
    (net (code "82") (name "Net-(J3-Pad4)") (class "Default")
      (node (ref "J3") (pin "4") (pinfunction "4_4") (pintype "passive"))
      (node (ref "R22") (pin "1") (pinfunction "1_1") (pintype "passive"))
    )
    (net (code "83") (name "Net-(J3-Pad8)") (class "Default")
      (node (ref "J3") (pin "8") (pinfunction "8_8") (pintype "passive"))
      (node (ref "J5") (pin "1") (pinfunction "1_1") (pintype "passive"))
    )
    (net (code "84") (name "Net-(P2-Pad8)") (class "Default")
      (node (ref "P2") (pin "8") (pintype "passive"))
      (node (ref "R7") (pin "2") (pintype "passive"))
    )
    (net (code "85") (name "Net-(P2-Pad9)") (class "Default")
      (node (ref "P2") (pin "9") (pintype "passive"))
      (node (ref "R8") (pin "2") (pintype "passive"))
    )
    (net (code "86") (name "Net-(P2-Pad12)") (class "Default")
      (node (ref "P2") (pin "12") (pintype "passive"))
      (node (ref "R9") (pin "2") (pintype "passive"))
    )
    (net (code "87") (name "Net-(R15-Pad2)") (class "Default")
      (node (ref "R15") (pin "2") (pintype "passive"))
      (node (ref "S2") (pin "2") (pinfunction "2_2") (pintype "passive"))
    )
    (net (code "88") (name "Net-(S1-COMMON)") (class "Default")
      (node (ref "F1") (pin "2") (pinfunction "2_2") (pintype "passive"))
      (node (ref "S1") (pin "1") (pinfunction "COMMON_1") (pintype "passive"))
    )
    (net (code "89") (name "V5V") (class "Default")
      (node (ref "C1") (pin "1") (pinfunction "1_1") (pintype "passive"))
      (node (ref "S1") (pin "2") (pinfunction "NC_2") (pintype "passive"))
      (node (ref "U1") (pin "3") (pinfunction "Vin_3") (pintype "passive"))
    )
    (net (code "90") (name "unconnected-(J1-SBU1-PadA8)") (class "Default")
      (node (ref "J1") (pin "A8") (pinfunction "SBU1_A8") (pintype "passive"))
    )
    (net (code "91") (name "unconnected-(J1-SBU2-PadB8)") (class "Default")
      (node (ref "J1") (pin "B8") (pinfunction "SBU2_B8") (pintype "passive"))
    )
    (net (code "92") (name "unconnected-(J3-Pad24)") (class "Default")
      (node (ref "J3") (pin "24") (pinfunction "24_24") (pintype "passive"))
    )
    (net (code "93") (name "unconnected-(J4-Pad21)") (class "Default")
      (node (ref "J4") (pin "21") (pinfunction "21_21") (pintype "passive"))
    )
    (net (code "94") (name "unconnected-(P2-Pad7)") (class "Default")
      (node (ref "P2") (pin "7") (pintype "passive"))
    )
    (net (code "95") (name "unconnected-(S1-NO-Pad3)") (class "Default")
      (node (ref "S1") (pin "3") (pinfunction "NO_3") (pintype "passive"))
    )
  )
)
